# Hpowerv2.net
KiCad netlist of a schematic drawn in Altium Designer
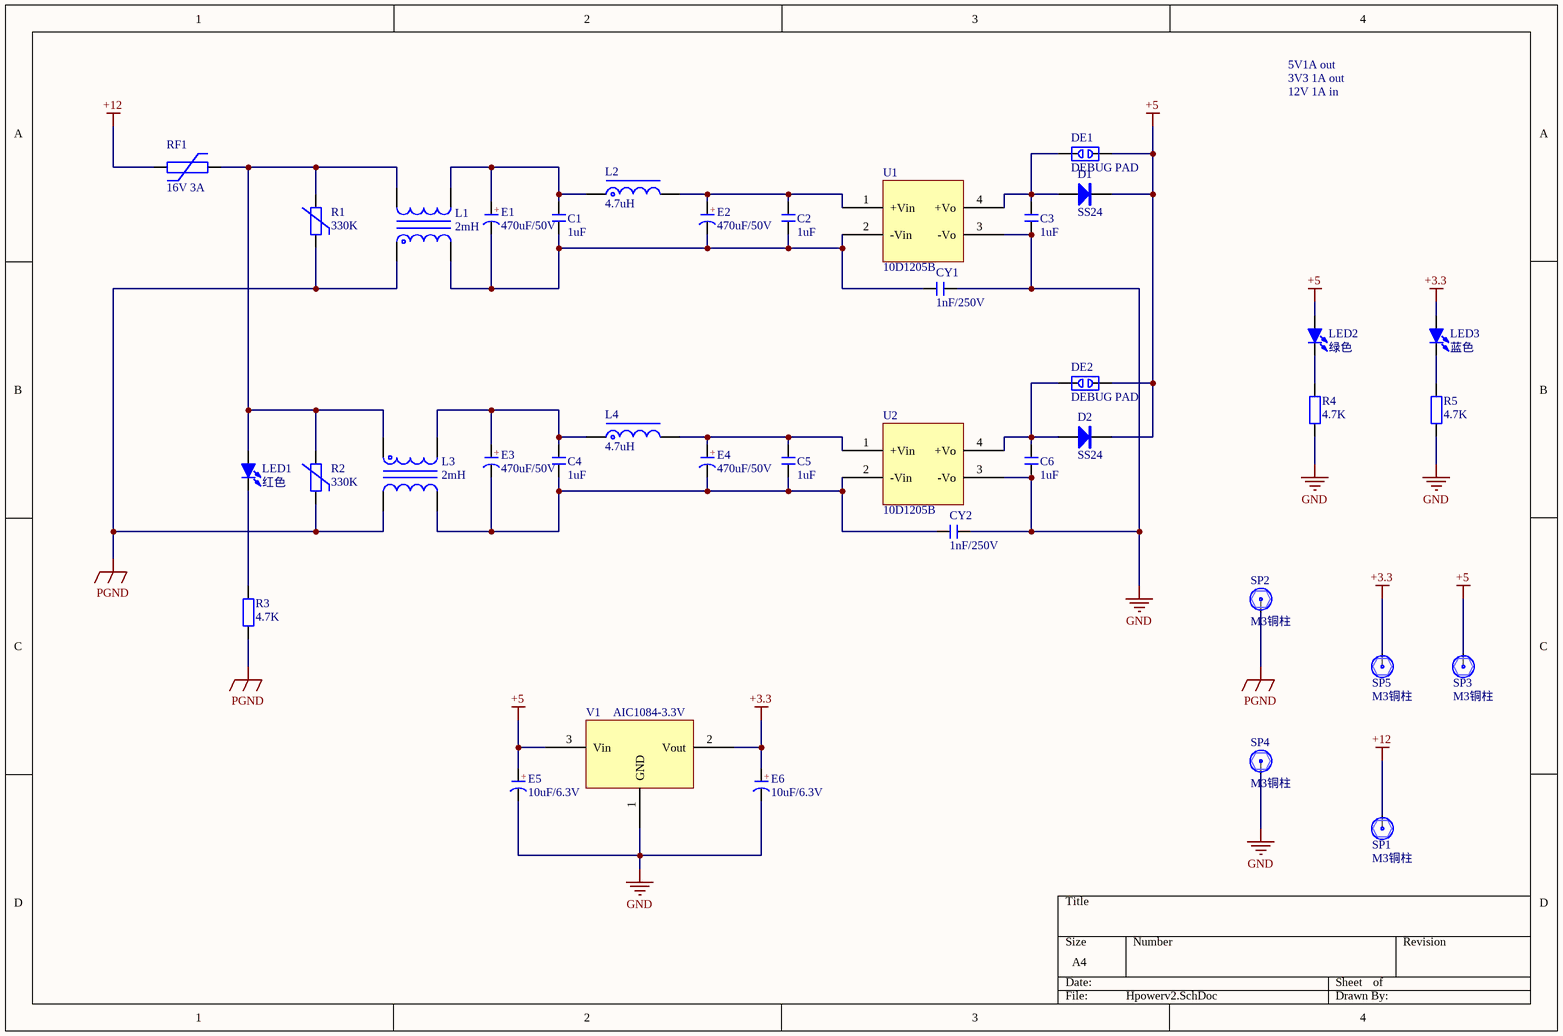
[diagram p0: Hpowerv2.SchDoc]

(export (version "E")
  (design (tool "Eeschema 10.0.6"))
  (components
    (comp (ref "C1")
      (value "1uF")
      (footprint "CC 2.2*5")
      (description "直插瓷片电容")
      (fields (field (name "版权归属") "源创客"))
      (libsource (lib "3.1   - 电阻-电容-电感") (part "C-CC"))
    )
    (comp (ref "C2")
      (value "1uF")
      (footprint "CC 2.2*5")
      (description "直插瓷片电容")
      (fields (field (name "版权归属") "源创客"))
      (libsource (lib "3.1   - 电阻-电容-电感") (part "C-CC"))
    )
    (comp (ref "C3")
      (value "1uF")
      (footprint "CC 2.2*5")
      (description "直插瓷片电容")
      (fields (field (name "版权归属") "源创客"))
      (libsource (lib "3.1   - 电阻-电容-电感") (part "C-CC"))
    )
    (comp (ref "C4")
      (value "1uF")
      (footprint "CC 2.2*5")
      (description "直插瓷片电容")
      (fields (field (name "版权归属") "源创客"))
      (libsource (lib "3.1   - 电阻-电容-电感") (part "C-CC"))
    )
    (comp (ref "C5")
      (value "1uF")
      (footprint "CC 2.2*5")
      (description "直插瓷片电容")
      (fields (field (name "版权归属") "源创客"))
      (libsource (lib "3.1   - 电阻-电容-电感") (part "C-CC"))
    )
    (comp (ref "C6")
      (value "1uF")
      (footprint "CC 2.2*5")
      (description "直插瓷片电容")
      (fields (field (name "版权归属") "源创客"))
      (libsource (lib "3.1   - 电阻-电容-电感") (part "C-CC"))
    )
    (comp (ref "CY1")
      (value "1nF/250V")
      (footprint "CY 7.5*10*4")
      (description "高压陶瓷电容，Y电容")
      (fields (field (name "版权归属") "源创客"))
      (libsource (lib "3.1   - 电阻-电容-电感") (part "C-CY"))
    )
    (comp (ref "CY2")
      (value "1nF/250V")
      (footprint "CY 7.5*10*4")
      (description "高压陶瓷电容，Y电容")
      (fields (field (name "版权归属") "源创客"))
      (libsource (lib "3.1   - 电阻-电容-电感") (part "C-CY"))
    )
    (comp (ref "D1")
      (value "SS24")
      (footprint "SMB")
      (description "肖特基二极管")
      (fields (field (name "版权归属") "源创客"))
      (libsource (lib "8.1   - 二极管-整流桥") (part "SS24"))
    )
    (comp (ref "D2")
      (value "SS24")
      (footprint "SMB")
      (description "肖特基二极管")
      (fields (field (name "版权归属") "源创客"))
      (libsource (lib "8.1   - 二极管-整流桥") (part "SS24"))
    )
    (comp (ref "DE1")
      (value "DEBUG PAD")
      (footprint "DEBUG_A")
      (description "调试断点焊盘")
      (fields (field (name "版权归属") "源创客"))
      (libsource (lib "15.1 - 未分类器件") (part "DEBUG"))
    )
    (comp (ref "DE2")
      (value "DEBUG PAD")
      (footprint "DEBUG_A")
      (description "调试断点焊盘")
      (fields (field (name "版权归属") "源创客"))
      (libsource (lib "15.1 - 未分类器件") (part "DEBUG"))
    )
    (comp (ref "E1")
      (value "470uF/50V")
      (footprint "CM G(12.5*13.5)")
      (description "贴片电解电容")
      (fields (field (name "版权归属") "源创客"))
      (libsource (lib "3.1   - 电阻-电容-电感") (part "C-CM"))
    )
    (comp (ref "E2")
      (value "470uF/50V")
      (footprint "CM G(12.5*13.5)")
      (description "贴片电解电容")
      (fields (field (name "版权归属") "源创客"))
      (libsource (lib "3.1   - 电阻-电容-电感") (part "C-CM"))
    )
    (comp (ref "E3")
      (value "470uF/50V")
      (footprint "CM G(12.5*13.5)")
      (description "贴片电解电容")
      (fields (field (name "版权归属") "源创客"))
      (libsource (lib "3.1   - 电阻-电容-电感") (part "C-CM"))
    )
    (comp (ref "E4")
      (value "470uF/50V")
      (footprint "CM G(12.5*13.5)")
      (description "贴片电解电容")
      (fields (field (name "版权归属") "源创客"))
      (libsource (lib "3.1   - 电阻-电容-电感") (part "C-CM"))
    )
    (comp (ref "E5")
      (value "10uF/6.3V")
      (footprint "CD A(3216)")
      (description "贴片钽电容")
      (fields (field (name "版权归属") "源创客"))
      (libsource (lib "3.1   - 电阻-电容-电感") (part "C-CD"))
    )
    (comp (ref "E6")
      (value "10uF/6.3V")
      (footprint "CD A(3216)")
      (description "贴片钽电容")
      (fields (field (name "版权归属") "源创客"))
      (libsource (lib "3.1   - 电阻-电容-电感") (part "C-CD"))
    )
    (comp (ref "L1")
      (value "2mH")
      (footprint "UU9.8")
      (description "共模电感")
      (fields (field (name "版权归属") "源创客"))
      (libsource (lib "") (part "L-CMC_1"))
    )
    (comp (ref "L2")
      (value "4.7uH")
      (footprint "NR5020")
      (description "NR磁胶电感")
      (fields (field (name "版权归属") "源创客"))
      (libsource (lib "3.1   - 电阻-电容-电感") (part "L-NR"))
    )
    (comp (ref "L3")
      (value "2mH")
      (footprint "UU9.8")
      (description "共模电感")
      (fields (field (name "版权归属") "源创客"))
      (libsource (lib "3.1   - 电阻-电容-电感") (part "L-CMC"))
    )
    (comp (ref "L4")
      (value "4.7uH")
      (footprint "NR5020")
      (description "NR磁胶电感")
      (fields (field (name "版权归属") "源创客"))
      (libsource (lib "3.1   - 电阻-电容-电感") (part "L-NR"))
    )
    (comp (ref "LED1")
      (value "红色")
      (footprint "LED 0603R")
      (description "贴片LED")
      (fields (field (name "版权归属") "源创客"))
      (libsource (lib "9.1   - LED") (part "LED-SMD"))
    )
    (comp (ref "LED2")
      (value "绿色")
      (footprint "LED 0603G")
      (description "贴片LED")
      (fields (field (name "版权归属") "源创客"))
      (libsource (lib "9.1   - LED") (part "LED-SMD"))
    )
    (comp (ref "LED3")
      (value "蓝色")
      (footprint "LED 0603B")
      (description "贴片LED")
      (fields (field (name "版权归属") "源创客"))
      (libsource (lib "9.1   - LED") (part "LED-SMD"))
    )
    (comp (ref "R1")
      (value "330K")
      (footprint "14D")
      (description "压敏电阻")
      (fields (field (name "版权归属") "源创客"))
      (libsource (lib "3.1   - 电阻-电容-电感") (part "R_VDR"))
    )
    (comp (ref "R2")
      (value "330K")
      (footprint "14D")
      (description "压敏电阻")
      (fields (field (name "版权归属") "源创客"))
      (libsource (lib "3.1   - 电阻-电容-电感") (part "R_VDR"))
    )
    (comp (ref "R3")
      (value "4.7K")
      (footprint "R 0603_M")
      (description "贴片电阻")
      (fields (field (name "版权归属") "源创客"))
      (libsource (lib "3.1   - 电阻-电容-电感") (part "R"))
    )
    (comp (ref "R4")
      (value "4.7K")
      (footprint "R 0603_M")
      (description "贴片电阻")
      (fields (field (name "版权归属") "源创客"))
      (libsource (lib "3.1   - 电阻-电容-电感") (part "R"))
    )
    (comp (ref "R5")
      (value "4.7K")
      (footprint "R 0603_M")
      (description "贴片电阻")
      (fields (field (name "版权归属") "源创客"))
      (libsource (lib "3.1   - 电阻-电容-电感") (part "R"))
    )
    (comp (ref "RF1")
      (value "16V 3A")
      (footprint "14D")
      (description "PPTC自恢复保险丝")
      (fields (field (name "版权归属") "源创客"))
      (libsource (lib "10.1 - 保险丝-晶振") (part "PPTC"))
    )
    (comp (ref "SP1")
      (value "M3铜柱")
      (footprint "M3x14_N")
      (description "铜柱")
      (fields (field (name "版权归属") "源创客"))
      (libsource (lib "15.1 - 未分类器件") (part "铜柱大焊盘"))
    )
    (comp (ref "SP2")
      (value "M3铜柱")
      (footprint "M3x14_N")
      (description "铜柱")
      (fields (field (name "版权归属") "源创客"))
      (libsource (lib "15.1 - 未分类器件") (part "铜柱大焊盘"))
    )
    (comp (ref "SP3")
      (value "M3铜柱")
      (footprint "M3x14_N")
      (description "铜柱")
      (fields (field (name "版权归属") "源创客"))
      (libsource (lib "15.1 - 未分类器件") (part "铜柱大焊盘"))
    )
    (comp (ref "SP4")
      (value "M3铜柱")
      (footprint "M3x14_N")
      (description "铜柱")
      (fields (field (name "版权归属") "源创客"))
      (libsource (lib "15.1 - 未分类器件") (part "铜柱大焊盘"))
    )
    (comp (ref "SP5")
      (value "M3铜柱")
      (footprint "M3x14_N")
      (description "铜柱")
      (fields (field (name "版权归属") "源创客"))
      (libsource (lib "15.1 - 未分类器件") (part "铜柱大焊盘"))
    )
    (comp (ref "U1")
      (value "10D1205B")
      (footprint "10D12B-10WDCDC")
      (description "DC-DC 12V转5V隔离降压模块")
      (libsource (lib "HLKPower") (part "10D1205B"))
    )
    (comp (ref "U2")
      (value "10D1205B")
      (footprint "10D12B-10WDCDC")
      (description "DC-DC 12V转5V隔离降压模块")
      (libsource (lib "HLKPower") (part "10D1205B"))
    )
    (comp (ref "V1")
      (value "AIC1084-3.3V")
      (footprint "TO263-3B")
      (description "大功率LDO")
      (libsource (lib "1.3   - 电源类芯片") (part "AIC1084"))
    )
  )
  (nets
    (net (code "1") (name "+3.3") (class "Default")
      (node (ref "E6") (pin "1") (pinfunction "A_1") (pintype "passive"))
      (node (ref "LED3") (pin "1") (pinfunction "A_1") (pintype "passive"))
      (node (ref "SP5") (pin "1") (pinfunction "1_1") (pintype "passive"))
      (node (ref "V1") (pin "2") (pinfunction "Vout_2") (pintype "passive"))
    )
    (net (code "2") (name "+5") (class "Default")
      (node (ref "D1") (pin "2") (pinfunction "K_2") (pintype "passive"))
      (node (ref "D2") (pin "2") (pinfunction "K_2") (pintype "passive"))
      (node (ref "DE1") (pin "2") (pinfunction "2_2") (pintype "passive"))
      (node (ref "DE2") (pin "2") (pinfunction "2_2") (pintype "passive"))
      (node (ref "E5") (pin "1") (pinfunction "A_1") (pintype "passive"))
      (node (ref "LED2") (pin "1") (pinfunction "A_1") (pintype "passive"))
      (node (ref "SP3") (pin "1") (pinfunction "1_1") (pintype "passive"))
      (node (ref "V1") (pin "3") (pinfunction "Vin_3") (pintype "passive"))
    )
    (net (code "3") (name "+12") (class "Default")
      (node (ref "RF1") (pin "1") (pinfunction "1_1") (pintype "passive"))
      (node (ref "SP1") (pin "1") (pinfunction "1_1") (pintype "passive"))
    )
    (net (code "4") (name "GND") (class "Default")
      (node (ref "C3") (pin "2") (pinfunction "2_2") (pintype "passive"))
      (node (ref "C6") (pin "2") (pinfunction "2_2") (pintype "passive"))
      (node (ref "CY1") (pin "2") (pinfunction "2_2") (pintype "passive"))
      (node (ref "CY2") (pin "2") (pinfunction "2_2") (pintype "passive"))
      (node (ref "E5") (pin "2") (pinfunction "K_2") (pintype "passive"))
      (node (ref "E6") (pin "2") (pinfunction "K_2") (pintype "passive"))
      (node (ref "R4") (pin "1") (pinfunction "1_1") (pintype "passive"))
      (node (ref "R5") (pin "1") (pinfunction "1_1") (pintype "passive"))
      (node (ref "SP4") (pin "1") (pinfunction "1_1") (pintype "passive"))
      (node (ref "U1") (pin "3") (pinfunction "-Vo_3") (pintype "passive"))
      (node (ref "U2") (pin "3") (pinfunction "-Vo_3") (pintype "passive"))
      (node (ref "V1") (pin "1") (pinfunction "GND_1") (pintype "passive"))
    )
    (net (code "5") (name "Net-(D1-A)") (class "Default")
      (node (ref "C3") (pin "1") (pinfunction "1_1") (pintype "passive"))
      (node (ref "D1") (pin "1") (pinfunction "A_1") (pintype "passive"))
      (node (ref "DE1") (pin "1") (pinfunction "1_1") (pintype "passive"))
      (node (ref "U1") (pin "4") (pinfunction "+Vo_4") (pintype "passive"))
    )
    (net (code "6") (name "Net-(D2-A)") (class "Default")
      (node (ref "C6") (pin "1") (pinfunction "1_1") (pintype "passive"))
      (node (ref "D2") (pin "1") (pinfunction "A_1") (pintype "passive"))
      (node (ref "DE2") (pin "1") (pinfunction "1_1") (pintype "passive"))
      (node (ref "U2") (pin "4") (pinfunction "+Vo_4") (pintype "passive"))
    )
    (net (code "7") (name "Net-(E1-A)") (class "Default")
      (node (ref "C1") (pin "1") (pinfunction "1_1") (pintype "passive"))
      (node (ref "E1") (pin "1") (pinfunction "A_1") (pintype "passive"))
      (node (ref "L1") (pin "3") (pinfunction "3_3") (pintype "passive"))
      (node (ref "L2") (pin "1") (pinfunction "1_1") (pintype "passive"))
    )
    (net (code "8") (name "Net-(E1-K)") (class "Default")
      (node (ref "C1") (pin "2") (pinfunction "2_2") (pintype "passive"))
      (node (ref "C2") (pin "2") (pinfunction "2_2") (pintype "passive"))
      (node (ref "CY1") (pin "1") (pinfunction "1_1") (pintype "passive"))
      (node (ref "E1") (pin "2") (pinfunction "K_2") (pintype "passive"))
      (node (ref "E2") (pin "2") (pinfunction "K_2") (pintype "passive"))
      (node (ref "L1") (pin "2") (pinfunction "2_2") (pintype "passive"))
      (node (ref "U1") (pin "2") (pinfunction "-Vin_2") (pintype "passive"))
    )
    (net (code "9") (name "Net-(E2-A)") (class "Default")
      (node (ref "C2") (pin "1") (pinfunction "1_1") (pintype "passive"))
      (node (ref "E2") (pin "1") (pinfunction "A_1") (pintype "passive"))
      (node (ref "L2") (pin "2") (pinfunction "2_2") (pintype "passive"))
      (node (ref "U1") (pin "1") (pinfunction "+Vin_1") (pintype "passive"))
    )
    (net (code "10") (name "Net-(E3-A)") (class "Default")
      (node (ref "C4") (pin "1") (pinfunction "1_1") (pintype "passive"))
      (node (ref "E3") (pin "1") (pinfunction "A_1") (pintype "passive"))
      (node (ref "L3") (pin "2") (pinfunction "2_2") (pintype "passive"))
      (node (ref "L4") (pin "1") (pinfunction "1_1") (pintype "passive"))
    )
    (net (code "11") (name "Net-(E3-K)") (class "Default")
      (node (ref "C4") (pin "2") (pinfunction "2_2") (pintype "passive"))
      (node (ref "C5") (pin "2") (pinfunction "2_2") (pintype "passive"))
      (node (ref "CY2") (pin "1") (pinfunction "1_1") (pintype "passive"))
      (node (ref "E3") (pin "2") (pinfunction "K_2") (pintype "passive"))
      (node (ref "E4") (pin "2") (pinfunction "K_2") (pintype "passive"))
      (node (ref "L3") (pin "3") (pinfunction "3_3") (pintype "passive"))
      (node (ref "U2") (pin "2") (pinfunction "-Vin_2") (pintype "passive"))
    )
    (net (code "12") (name "Net-(E4-A)") (class "Default")
      (node (ref "C5") (pin "1") (pinfunction "1_1") (pintype "passive"))
      (node (ref "E4") (pin "1") (pinfunction "A_1") (pintype "passive"))
      (node (ref "L4") (pin "2") (pinfunction "2_2") (pintype "passive"))
      (node (ref "U2") (pin "1") (pinfunction "+Vin_1") (pintype "passive"))
    )
    (net (code "13") (name "Net-(LED1-A)") (class "Default")
      (node (ref "L1") (pin "4") (pinfunction "4_4") (pintype "passive"))
      (node (ref "L3") (pin "1") (pinfunction "1_1") (pintype "passive"))
      (node (ref "LED1") (pin "1") (pinfunction "A_1") (pintype "passive"))
      (node (ref "R1") (pin "2") (pinfunction "2_2") (pintype "passive"))
      (node (ref "R2") (pin "2") (pinfunction "2_2") (pintype "passive"))
      (node (ref "RF1") (pin "2") (pinfunction "2_2") (pintype "passive"))
    )
    (net (code "14") (name "Net-(LED1-K)") (class "Default")
      (node (ref "LED1") (pin "2") (pinfunction "K_2") (pintype "passive"))
      (node (ref "R3") (pin "2") (pinfunction "2_2") (pintype "passive"))
    )
    (net (code "15") (name "Net-(LED2-K)") (class "Default")
      (node (ref "LED2") (pin "2") (pinfunction "K_2") (pintype "passive"))
      (node (ref "R4") (pin "2") (pinfunction "2_2") (pintype "passive"))
    )
    (net (code "16") (name "Net-(LED3-K)") (class "Default")
      (node (ref "LED3") (pin "2") (pinfunction "K_2") (pintype "passive"))
      (node (ref "R5") (pin "2") (pinfunction "2_2") (pintype "passive"))
    )
    (net (code "17") (name "PGND") (class "Default")
      (node (ref "L1") (pin "1") (pinfunction "1_1") (pintype "passive"))
      (node (ref "L3") (pin "4") (pinfunction "4_4") (pintype "passive"))
      (node (ref "R1") (pin "1") (pinfunction "1_1") (pintype "passive"))
      (node (ref "R2") (pin "1") (pinfunction "1_1") (pintype "passive"))
      (node (ref "R3") (pin "1") (pinfunction "1_1") (pintype "passive"))
      (node (ref "SP2") (pin "1") (pinfunction "1_1") (pintype "passive"))
    )
  )
)
